# RGB_Plugin_Board.net
KiCad netlist of a schematic drawn in Altium Designer
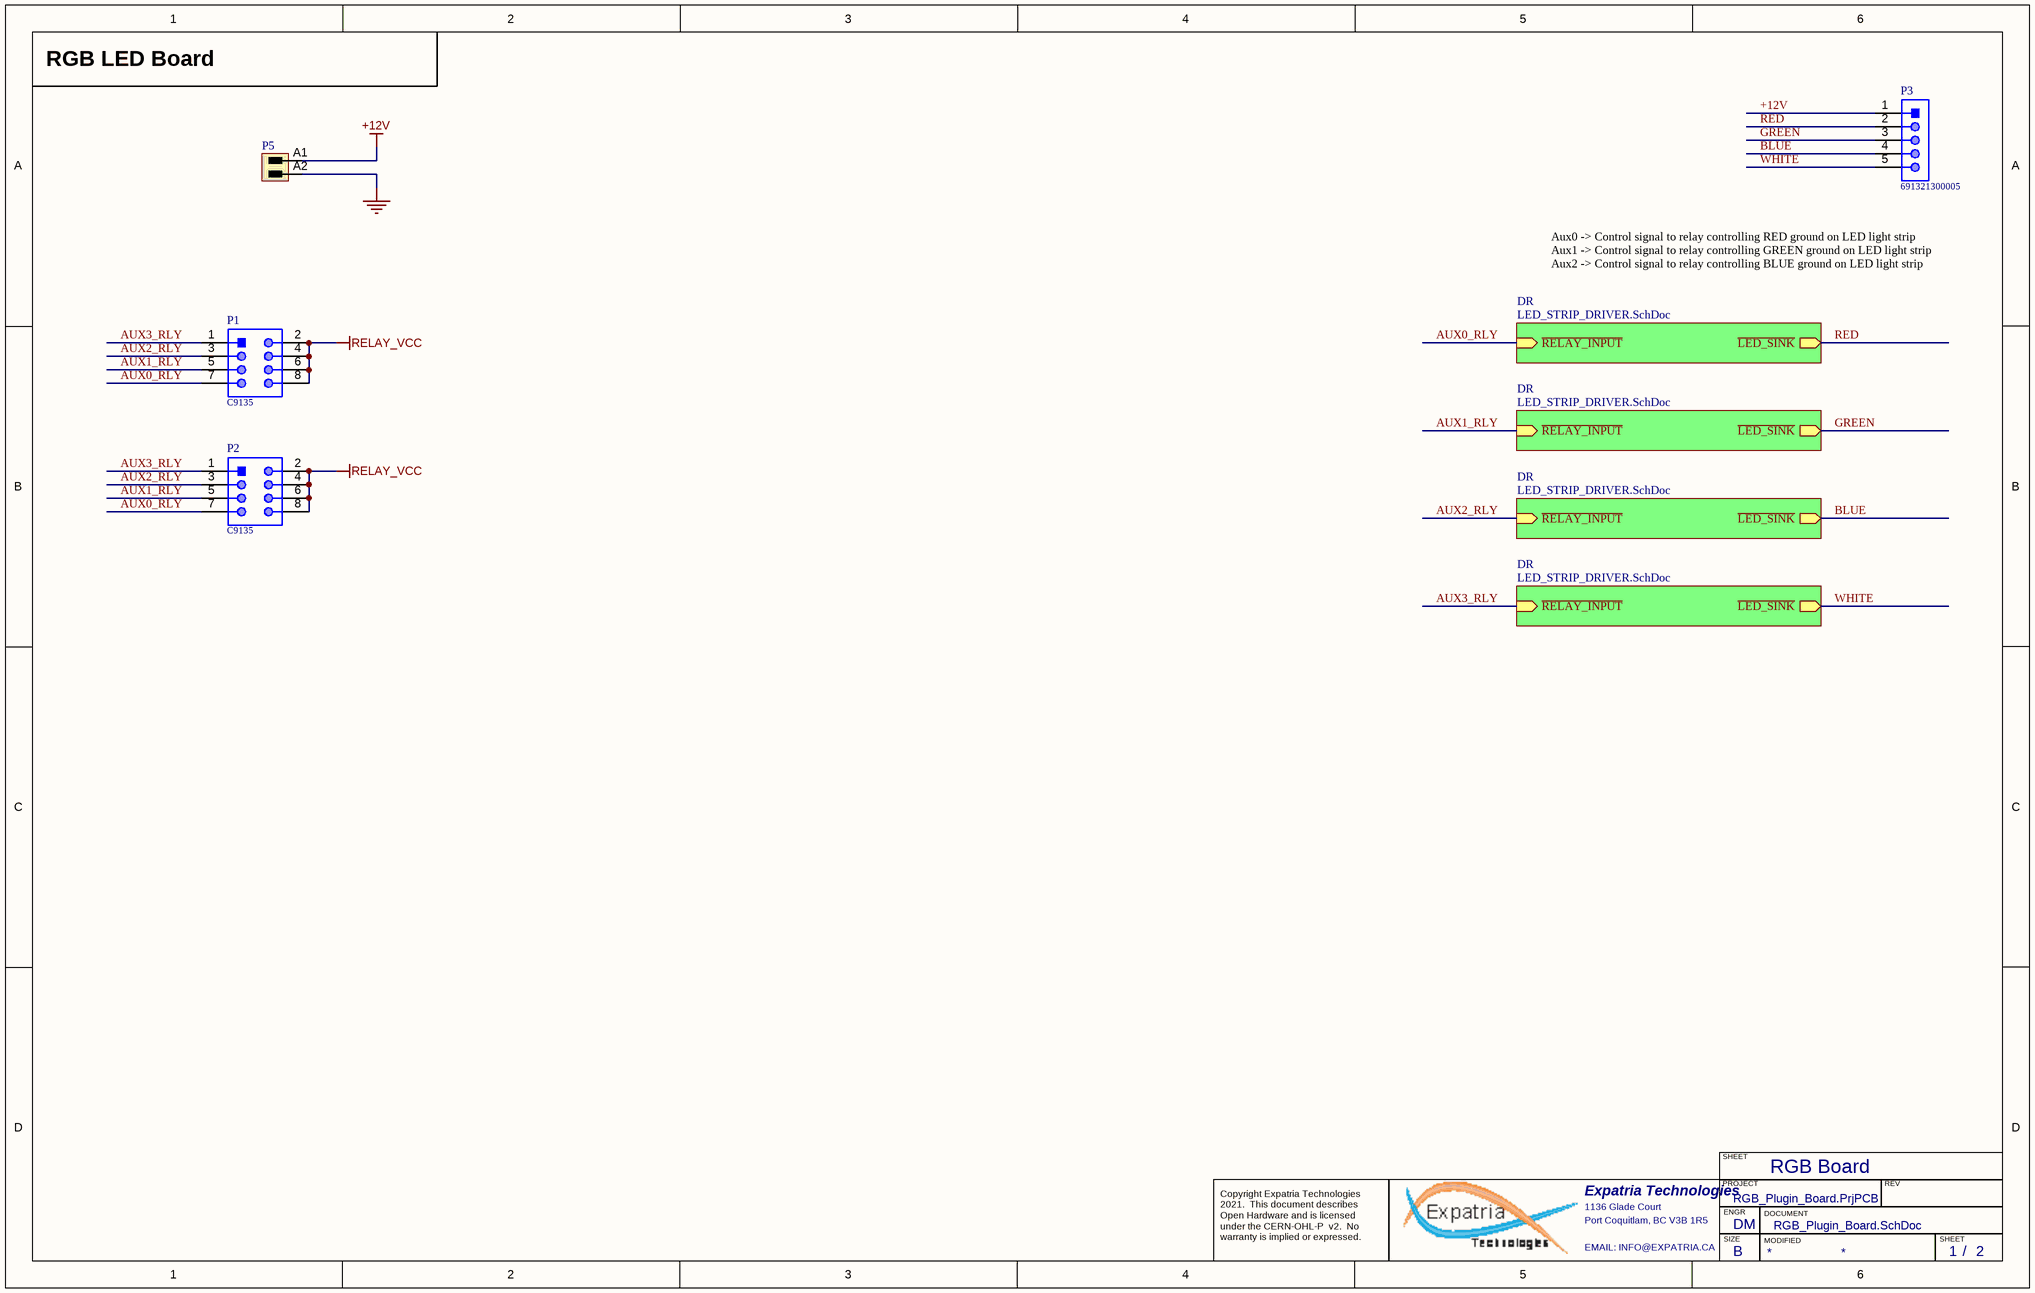
[diagram p0: RGB_Plugin_Board.SchDoc]

(export (version "E")
  (design (tool "Eeschema 10.0.6"))
  (components
    (comp (ref "P1")
      (value "C9135")
      (footprint "61200821621")
      (description "Male Box Header WR-BHD, THT, Vertical, pitch 2.54 mm, 8 pins")
      (fields (field (name "MANUFACTURER") "Wurth Elektronik") (field (name "PUBLISHER") "WurthElektronik"))
      (libsource (lib "PrintNC_GRBLHAL_Breakout") (part "WE-CN-2P-M-R8"))
    )
    (comp (ref "P2")
      (value "C9135")
      (footprint "61200821621")
      (description "Male Box Header WR-BHD, THT, Vertical, pitch 2.54 mm, 8 pins")
      (fields (field (name "MANUFACTURER") "Wurth Elektronik") (field (name "PUBLISHER") "WurthElektronik"))
      (libsource (lib "PrintNC_GRBLHAL_Breakout") (part "WE-CN-2P-M-R8"))
    )
    (comp (ref "P3")
      (value "691321300005")
      (footprint "691321300005")
      (description "Serie 321 - 3.81mm Vertical PCB Header WR-TBL, 5 pin")
      (fields (field (name "MANUFACTURER") "Wurth Elektronik") (field (name "PUBLISHER") "WurthElektronik"))
      (libsource (lib "Altium Content Vault") (part "WE-CN-1P-M-R5"))
    )
    (comp (ref "P5")
      (value "~")
      (footprint "SL_3_50_180G_02")
      (fields
        (field (name "PARTNUMBER") "WJ15EDGVC-3.5-2P")
        (field (name "MANUFACTURER") "Ningbo Kangnex Elec")
      )
      (libsource (lib "PrintNC_GRBLHAL_Breakout") (part "Header_Male_02_1x02"))
    )
  )
  (nets
    (net (code "1") (name "+12V") (class "Default")
      (node (ref "P3") (pin "1") (pinfunction "1_1") (pintype "passive"))
      (node (ref "P5") (pin "A1") (pinfunction "A1_A1") (pintype "passive"))
    )
    (net (code "2") (name "/AUX0_RLY") (class "Default")
      (node (ref "P1") (pin "7") (pinfunction "7_7") (pintype "passive"))
      (node (ref "P2") (pin "7") (pinfunction "7_7") (pintype "passive"))
    )
    (net (code "3") (name "/AUX1_RLY") (class "Default")
      (node (ref "P1") (pin "5") (pinfunction "5_5") (pintype "passive"))
      (node (ref "P2") (pin "5") (pinfunction "5_5") (pintype "passive"))
    )
    (net (code "4") (name "/AUX2_RLY") (class "Default")
      (node (ref "P1") (pin "3") (pinfunction "3_3") (pintype "passive"))
      (node (ref "P2") (pin "3") (pinfunction "3_3") (pintype "passive"))
    )
    (net (code "5") (name "/AUX3_RLY") (class "Default")
      (node (ref "P1") (pin "1") (pinfunction "1_1") (pintype "passive"))
      (node (ref "P2") (pin "1") (pinfunction "1_1") (pintype "passive"))
    )
    (net (code "6") (name "/BLUE") (class "Default")
      (node (ref "P3") (pin "4") (pinfunction "4_4") (pintype "passive"))
    )
    (net (code "7") (name "/GREEN") (class "Default")
      (node (ref "P3") (pin "3") (pinfunction "3_3") (pintype "passive"))
    )
    (net (code "8") (name "/RED") (class "Default")
      (node (ref "P3") (pin "2") (pinfunction "2_2") (pintype "passive"))
    )
    (net (code "9") (name "/WHITE") (class "Default")
      (node (ref "P3") (pin "5") (pinfunction "5_5") (pintype "passive"))
    )
    (net (code "10") (name "GND") (class "Default")
      (node (ref "P5") (pin "A2") (pinfunction "A2_A2") (pintype "passive"))
    )
    (net (code "11") (name "RELAY_VCC") (class "Default")
      (node (ref "P1") (pin "2") (pinfunction "2_2") (pintype "passive"))
      (node (ref "P1") (pin "4") (pinfunction "4_4") (pintype "passive"))
      (node (ref "P1") (pin "6") (pinfunction "6_6") (pintype "passive"))
      (node (ref "P1") (pin "8") (pinfunction "8_8") (pintype "passive"))
      (node (ref "P2") (pin "2") (pinfunction "2_2") (pintype "passive"))
      (node (ref "P2") (pin "4") (pinfunction "4_4") (pintype "passive"))
      (node (ref "P2") (pin "6") (pinfunction "6_6") (pintype "passive"))
      (node (ref "P2") (pin "8") (pinfunction "8_8") (pintype "passive"))
    )
  )
)
